# CTD_V02.net
KiCad netlist of a schematic drawn in EAGLE
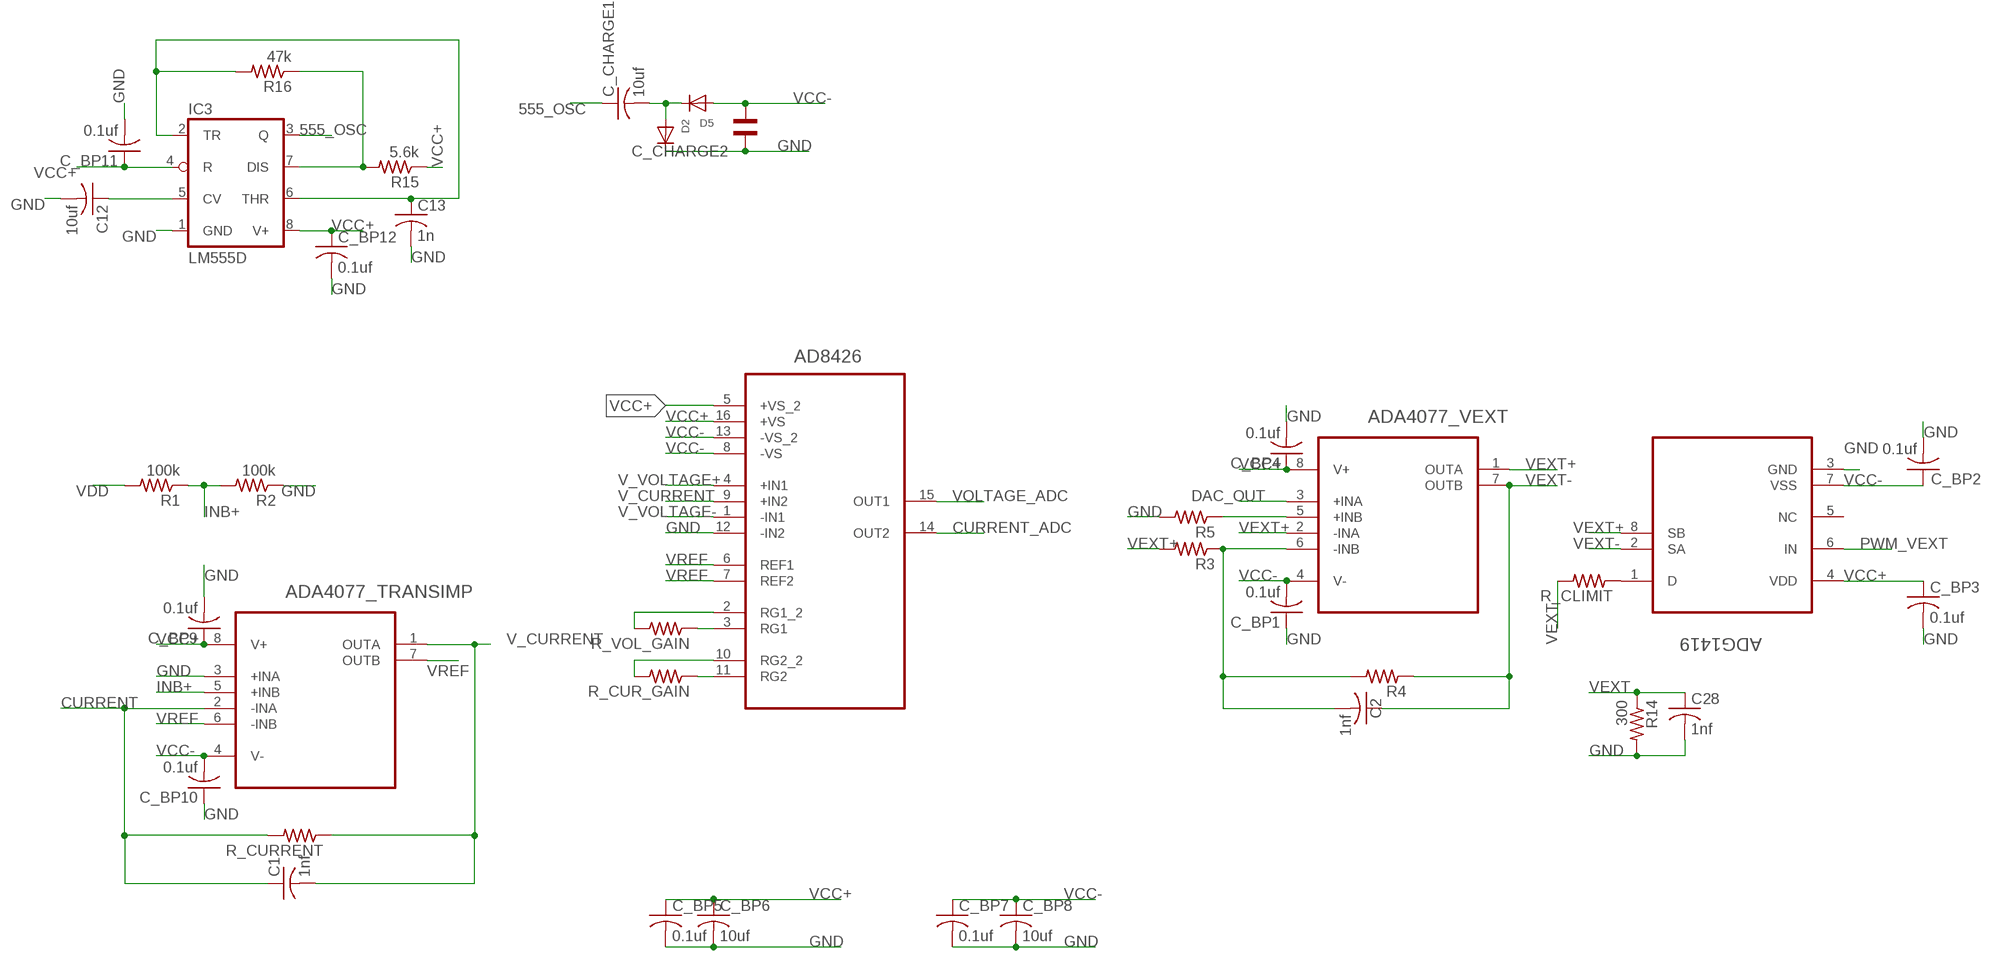
[diagram p0: schematic, sheet 1]
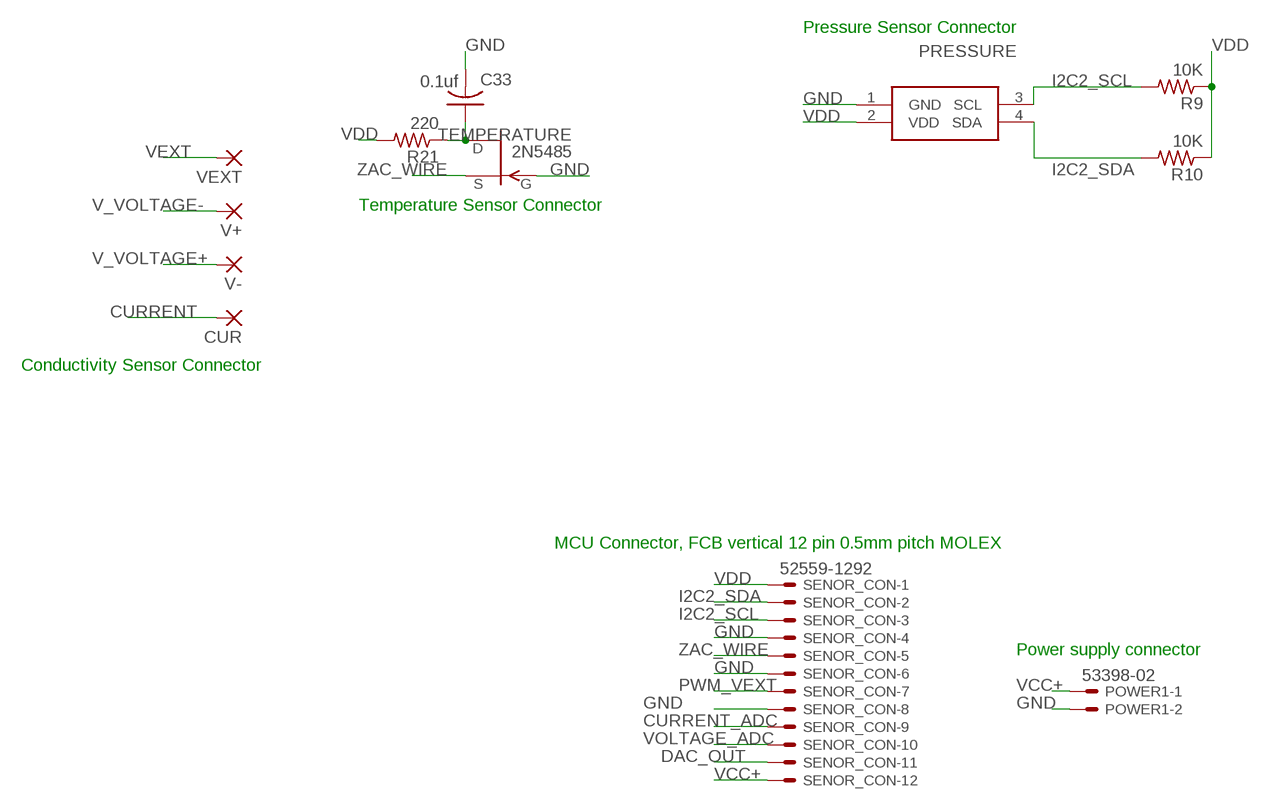
[diagram p1: schematic, sheet 2]
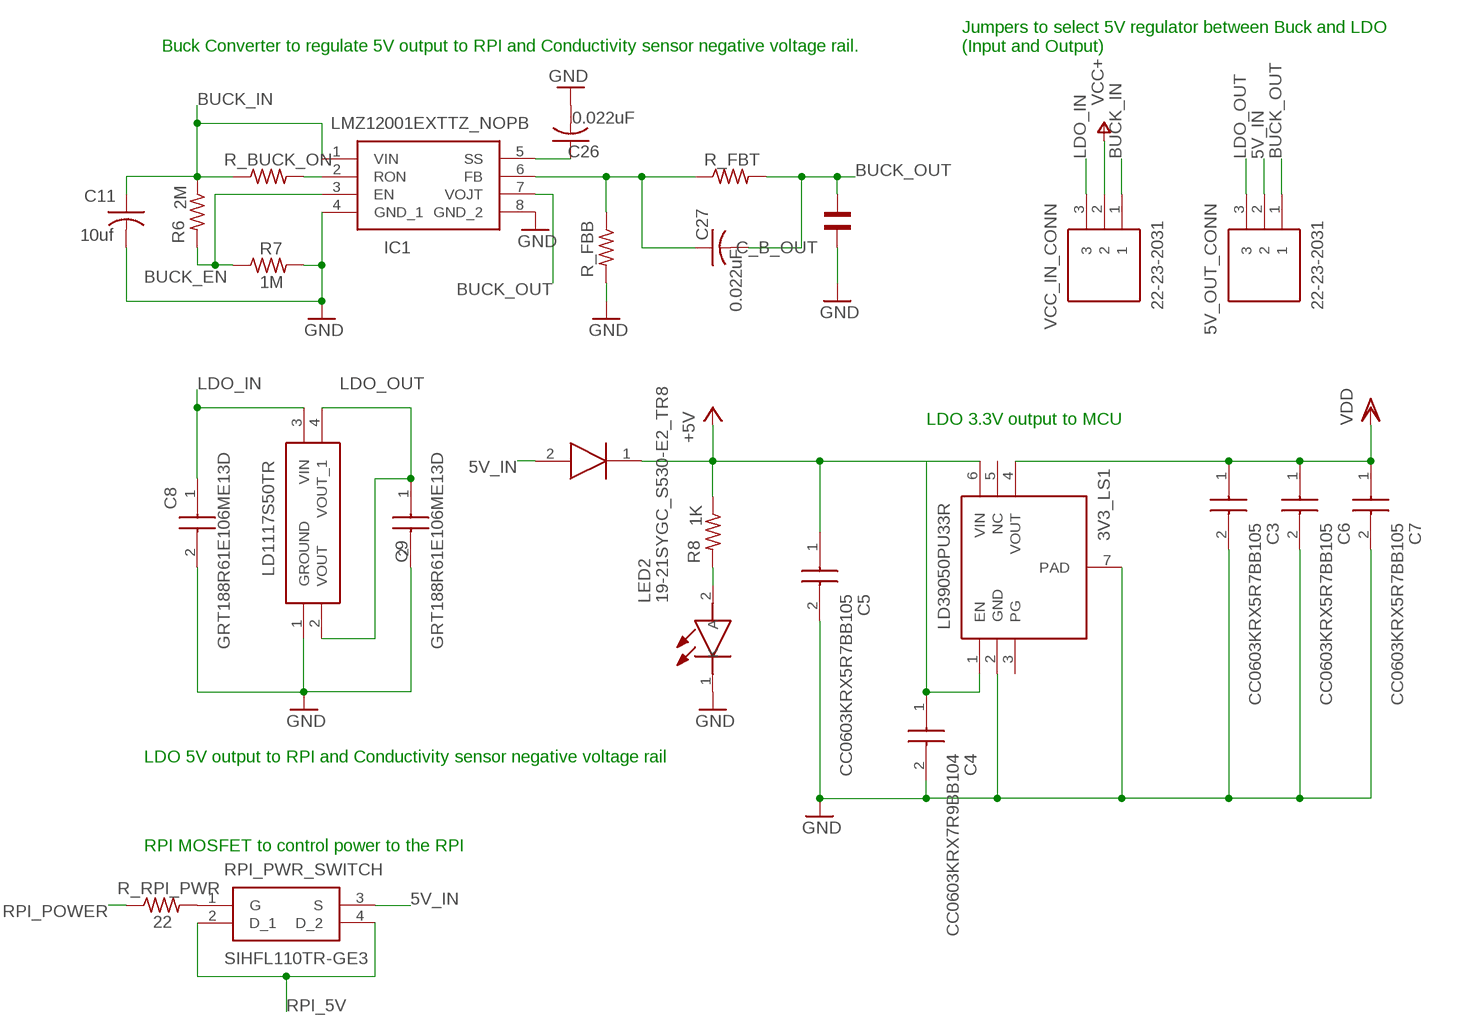
[diagram p2: schematic, sheet 3]
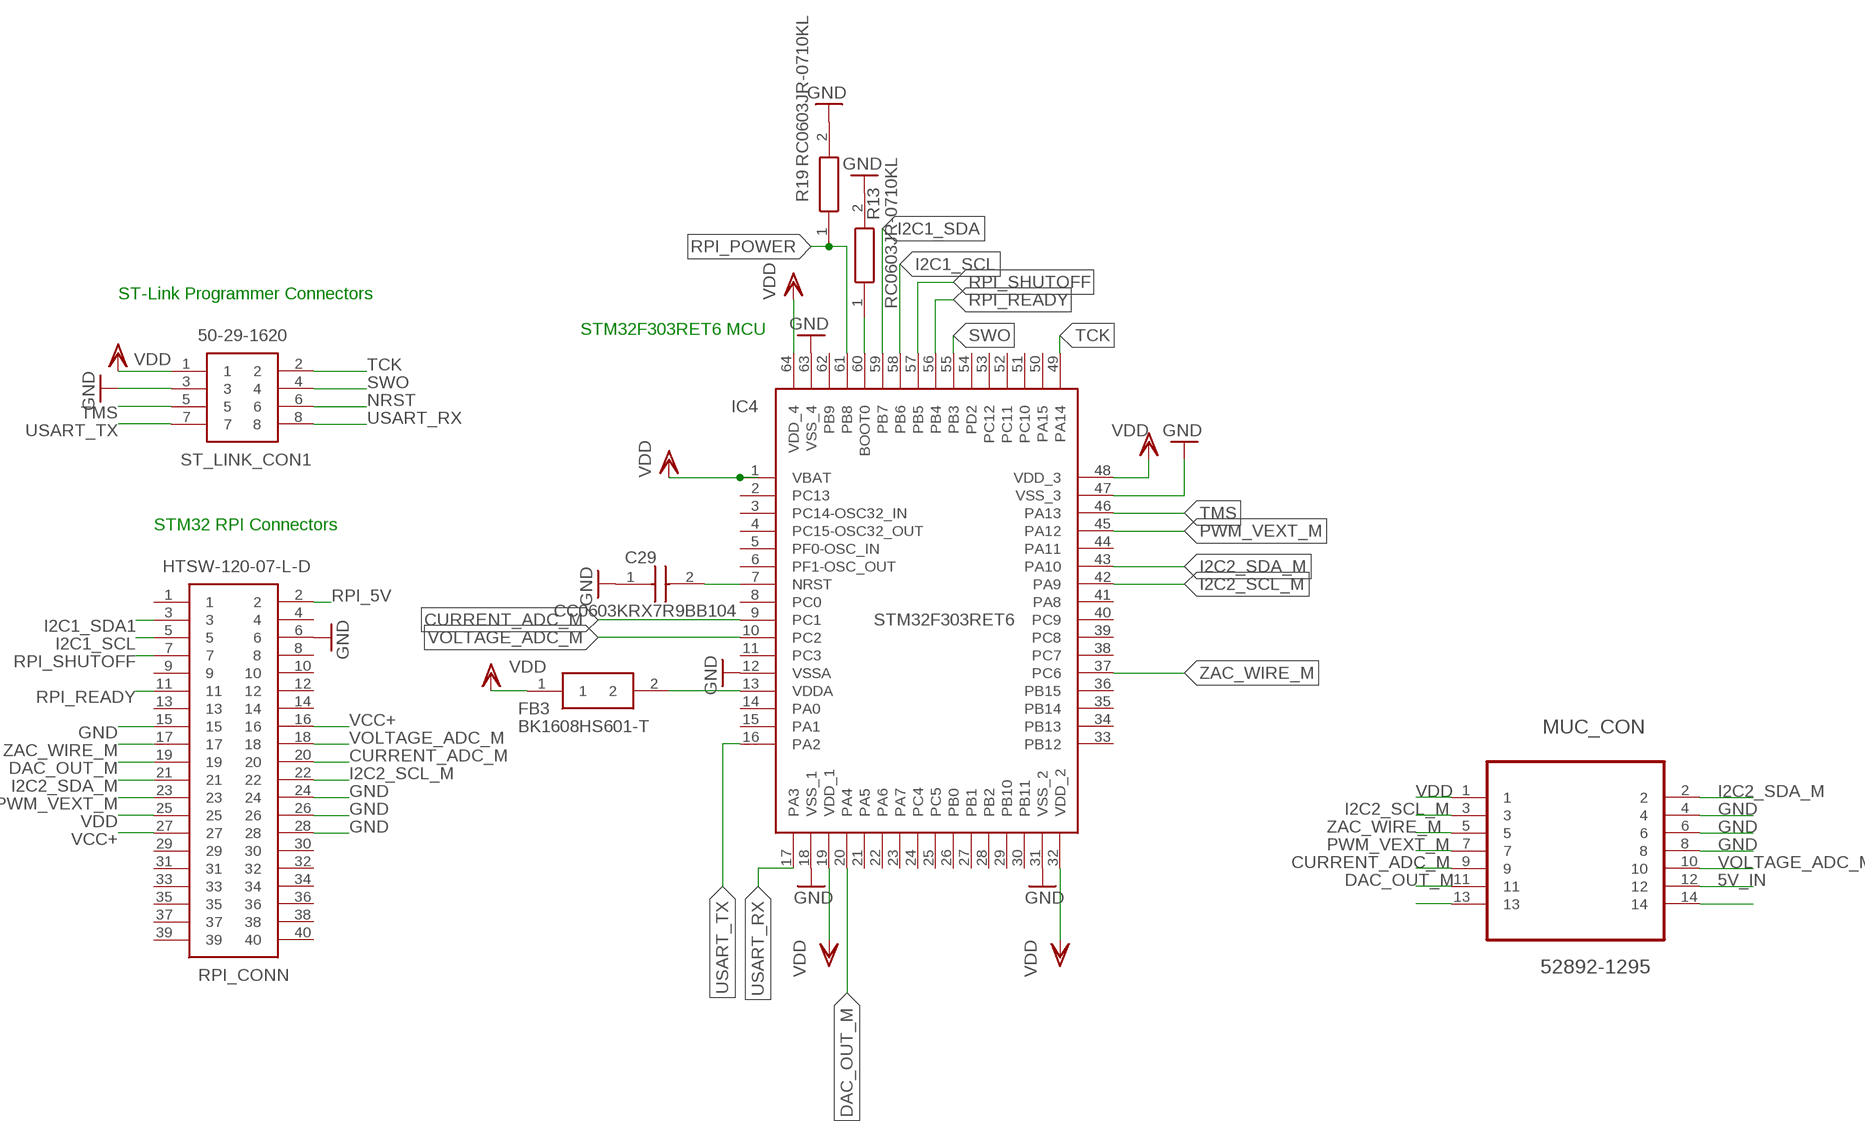
[diagram p3: schematic, sheet 4]

(export (version "E")
  (design (tool "Eeschema 10.0.6"))
  (components
    (comp (ref "C33")
      (value "0.1uf")
      (footprint "eagle-import:C0603")
      (libsource (lib "eagle-import") (part "C-USC0603"))
    )
    (comp (ref "CUR")
      (value "SMD2")
      (footprint "eagle-import:SMD1,27-2,54")
      (libsource (lib "eagle-import") (part "SMD2"))
    )
    (comp (ref "POWER1")
      (value "53398-02")
      (footprint "eagle-import:53398-02")
      (fields (field (name "MF") "MOLEX"))
      (libsource (lib "eagle-import") (part "53?-02398"))
    )
    (comp (ref "PRESSURE")
      (value "MS583702BA01-50")
      (footprint "eagle-import:MS583702BA0150")
      (fields (field (name "MOUSER_PART_NUMBER") "824-MS583702BA01-50"))
      (libsource (lib "eagle-import") (part "MS583702BA01-50"))
    )
    (comp (ref "R9")
      (value "10K")
      (footprint "eagle-import:R0603")
      (libsource (lib "eagle-import") (part "R-US_R0603"))
    )
    (comp (ref "R10")
      (value "10K")
      (footprint "eagle-import:R0603")
      (libsource (lib "eagle-import") (part "R-US_R0603"))
    )
    (comp (ref "R21")
      (value "220")
      (footprint "eagle-import:R0603")
      (libsource (lib "eagle-import") (part "R-US_R0603"))
    )
    (comp (ref "SENOR_CON")
      (value "52559-1292")
      (footprint "eagle-import:52559-1292")
      (fields (field (name "MF") "MOLEX"))
      (libsource (lib "eagle-import") (part "52559-1292"))
    )
    (comp (ref "TEMPERATURE")
      (value "2N5485")
      (footprint "eagle-import:TO92-")
      (libsource (lib "eagle-import") (part "?5482N5"))
    )
    (comp (ref "V+")
      (value "SMD2")
      (footprint "eagle-import:SMD1,27-2,54")
      (libsource (lib "eagle-import") (part "SMD2"))
    )
    (comp (ref "V-")
      (value "SMD2")
      (footprint "eagle-import:SMD1,27-2,54")
      (libsource (lib "eagle-import") (part "SMD2"))
    )
    (comp (ref "VEXT")
      (value "SMD2")
      (footprint "eagle-import:SMD1,27-2,54")
      (libsource (lib "eagle-import") (part "SMD2"))
    )
    (comp (ref "AD8426")
      (value "AD8426BCPZ-WP")
      (footprint "eagle-import:QFN65P400X400X100-16N")
      (fields (field (name "MF") "Analog Devices"))
      (libsource (lib "eagle-import") (part "AD8426BCPZ-WP"))
    )
    (comp (ref "ADA4077_TRANSIMP")
      (value "ADA4075-2ARZ")
      (footprint "eagle-import:SOIC127P600X175-8N")
      (fields (field (name "MPN") "ADA4077"))
      (libsource (lib "eagle-import") (part "ADA4075-2ARZ"))
    )
    (comp (ref "ADA4077_VEXT")
      (value "ADA4075-2ARZ")
      (footprint "eagle-import:SOIC127P600X175-8N")
      (fields (field (name "MPN") "ADA4077"))
      (libsource (lib "eagle-import") (part "ADA4075-2ARZ"))
    )
    (comp (ref "ADG1419")
      (value "ADG1419BRMZ")
      (footprint "eagle-import:SOP65P490X110-8N")
      (libsource (lib "eagle-import") (part "ADG1419BRMZ"))
    )
    (comp (ref "C1")
      (value "1nf")
      (footprint "eagle-import:C0603")
      (libsource (lib "eagle-import") (part "C-USC0603"))
    )
    (comp (ref "C2")
      (value "1nf")
      (footprint "eagle-import:C0603")
      (libsource (lib "eagle-import") (part "C-USC0603"))
    )
    (comp (ref "C12")
      (value "10uf")
      (footprint "eagle-import:C0603")
      (libsource (lib "eagle-import") (part "C-USC0603"))
    )
    (comp (ref "C13")
      (value "1n")
      (footprint "eagle-import:C0603")
      (libsource (lib "eagle-import") (part "C-USC0603"))
    )
    (comp (ref "C28")
      (value "1nf")
      (footprint "eagle-import:C0603")
      (libsource (lib "eagle-import") (part "C-USC0603"))
    )
    (comp (ref "C_BP1")
      (value "0.1uf")
      (footprint "eagle-import:C0603")
      (libsource (lib "eagle-import") (part "C-USC0603"))
    )
    (comp (ref "C_BP2")
      (value "0.1uf")
      (footprint "eagle-import:C0603")
      (libsource (lib "eagle-import") (part "C-USC0603"))
    )
    (comp (ref "C_BP3")
      (value "0.1uf")
      (footprint "eagle-import:C0603")
      (libsource (lib "eagle-import") (part "C-USC0603"))
    )
    (comp (ref "C_BP4")
      (value "0.1uf")
      (footprint "eagle-import:C0603")
      (libsource (lib "eagle-import") (part "C-USC0603"))
    )
    (comp (ref "C_BP5")
      (value "0.1uf")
      (footprint "eagle-import:C0603")
      (libsource (lib "eagle-import") (part "C-USC0603"))
    )
    (comp (ref "C_BP6")
      (value "10uf")
      (footprint "eagle-import:C0603")
      (libsource (lib "eagle-import") (part "C-USC0603"))
    )
    (comp (ref "C_BP7")
      (value "0.1uf")
      (footprint "eagle-import:C0603")
      (libsource (lib "eagle-import") (part "C-USC0603"))
    )
    (comp (ref "C_BP8")
      (value "10uf")
      (footprint "eagle-import:C0603")
      (libsource (lib "eagle-import") (part "C-USC0603"))
    )
    (comp (ref "C_BP9")
      (value "0.1uf")
      (footprint "eagle-import:C0603")
      (libsource (lib "eagle-import") (part "C-USC0603"))
    )
    (comp (ref "C_BP10")
      (value "0.1uf")
      (footprint "eagle-import:C0603")
      (libsource (lib "eagle-import") (part "C-USC0603"))
    )
    (comp (ref "C_BP11")
      (value "0.1uf")
      (footprint "eagle-import:C0603")
      (libsource (lib "eagle-import") (part "C-USC0603"))
    )
    (comp (ref "C_BP12")
      (value "0.1uf")
      (footprint "eagle-import:C0603")
      (libsource (lib "eagle-import") (part "C-USC0603"))
    )
    (comp (ref "C_CHARGE1")
      (value "10uf")
      (footprint "eagle-import:C0603")
      (libsource (lib "eagle-import") (part "C-USC0603"))
    )
    (comp (ref "C_CHARGE2")
      (value "WCAP-CSGP_1206_885012008001")
      (footprint "eagle-import:WCAP-CSGP_1206")
      (libsource (lib "eagle-import") (part "WCAP-CSGP_1206_885012008001"))
    )
    (comp (ref "D2")
      (value "DIODESOD-123")
      (footprint "eagle-import:SOD-123")
      (libsource (lib "eagle-import") (part "DIODESOD-123"))
    )
    (comp (ref "D5")
      (value "DIODESOD-123")
      (footprint "eagle-import:SOD-123")
      (libsource (lib "eagle-import") (part "DIODESOD-123"))
    )
    (comp (ref "IC3")
      (value "LM555D")
      (footprint "eagle-import:SO08")
      (libsource (lib "eagle-import") (part "555DLM"))
    )
    (comp (ref "R1")
      (value "100k")
      (footprint "eagle-import:R0603")
      (libsource (lib "eagle-import") (part "R-US_R0603"))
    )
    (comp (ref "R2")
      (value "100k")
      (footprint "eagle-import:R0603")
      (libsource (lib "eagle-import") (part "R-US_R0603"))
    )
    (comp (ref "R3")
      (value "R-US_R0603")
      (footprint "eagle-import:R0603")
      (libsource (lib "eagle-import") (part "R-US_R0603"))
    )
    (comp (ref "R4")
      (value "R-US_R0603")
      (footprint "eagle-import:R0603")
      (libsource (lib "eagle-import") (part "R-US_R0603"))
    )
    (comp (ref "R5")
      (value "R-US_R0603")
      (footprint "eagle-import:R0603")
      (libsource (lib "eagle-import") (part "R-US_R0603"))
    )
    (comp (ref "R14")
      (value "300")
      (footprint "eagle-import:R0603")
      (libsource (lib "eagle-import") (part "R-US_R0603"))
    )
    (comp (ref "R15")
      (value "5.6k")
      (footprint "eagle-import:R0603")
      (libsource (lib "eagle-import") (part "R-US_R0603"))
    )
    (comp (ref "R16")
      (value "47k")
      (footprint "eagle-import:R0603")
      (libsource (lib "eagle-import") (part "R-US_R0603"))
    )
    (comp (ref "R_CLIMIT")
      (value "R-US_R0603")
      (footprint "eagle-import:R0603")
      (libsource (lib "eagle-import") (part "R-US_R0603"))
    )
    (comp (ref "R_CURRENT")
      (value "R-US_R0603")
      (footprint "eagle-import:R0603")
      (libsource (lib "eagle-import") (part "R-US_R0603"))
    )
    (comp (ref "R_CUR_GAIN")
      (value "R-US_R0603")
      (footprint "eagle-import:R0603")
      (libsource (lib "eagle-import") (part "R-US_R0603"))
    )
    (comp (ref "R_VOL_GAIN")
      (value "R-US_R0603")
      (footprint "eagle-import:R0603")
      (libsource (lib "eagle-import") (part "R-US_R0603"))
    )
    (comp (ref "3V3_LS1")
      (value "LD39050PU33R")
      (footprint "eagle-import:SON95P300X300X100-7N")
      (fields (field (name "MOUSER_PART_NUMBER") "511-LD39050PU33R"))
      (libsource (lib "eagle-import") (part "LD39050PU33R"))
    )
    (comp (ref "5V_LS1")
      (value "LD1117S50TR")
      (footprint "eagle-import:SOT230P700X190-4N")
      (fields (field (name "MOUSER_PART_NUMBER") "511-LD1117S50"))
      (libsource (lib "eagle-import") (part "LD1117S50TR"))
    )
    (comp (ref "5V_OUT_CONN")
      (value "22-23-2031")
      (footprint "eagle-import:SHDR3W87P0X254_1X3_747X635X843")
      (fields (field (name "MOUSER_PART_NUMBER") "538-22-23-2031"))
      (libsource (lib "eagle-import") (part "22-23-2031"))
    )
    (comp (ref "C3")
      (value "CC0603KRX5R7BB105")
      (footprint "eagle-import:CAPC1608X90N")
      (fields (field (name "MOUSER_PART_NUMBER") "603-CC603KRX5R7BB105"))
      (libsource (lib "eagle-import") (part "CC0603KRX5R7BB105"))
    )
    (comp (ref "C4")
      (value "CC0603KRX7R9BB104")
      (footprint "eagle-import:CAPC1608X90N")
      (fields (field (name "MOUSER_PART_NUMBER") "603-CC603KRX7R9BB104"))
      (libsource (lib "eagle-import") (part "CC0603KRX7R9BB104"))
    )
    (comp (ref "C5")
      (value "CC0603KRX5R7BB105")
      (footprint "eagle-import:CAPC1608X90N")
      (fields (field (name "MOUSER_PART_NUMBER") "603-CC603KRX5R7BB105"))
      (libsource (lib "eagle-import") (part "CC0603KRX5R7BB105"))
    )
    (comp (ref "C6")
      (value "CC0603KRX5R7BB105")
      (footprint "eagle-import:CAPC1608X90N")
      (fields (field (name "MOUSER_PART_NUMBER") "603-CC603KRX5R7BB105"))
      (libsource (lib "eagle-import") (part "CC0603KRX5R7BB105"))
    )
    (comp (ref "C7")
      (value "CC0603KRX5R7BB105")
      (footprint "eagle-import:CAPC1608X90N")
      (fields (field (name "MOUSER_PART_NUMBER") "603-CC603KRX5R7BB105"))
      (libsource (lib "eagle-import") (part "CC0603KRX5R7BB105"))
    )
    (comp (ref "C8")
      (value "GRT188R61E106ME13D")
      (footprint "eagle-import:CAPC1608X100N")
      (fields (field (name "MOUSER_PART_NUMBER") "81-GRT188R61E106ME3D"))
      (libsource (lib "eagle-import") (part "GRT188R61E106ME13D"))
    )
    (comp (ref "C9")
      (value "GRT188R61E106ME13D")
      (footprint "eagle-import:CAPC1608X100N")
      (fields (field (name "MOUSER_PART_NUMBER") "81-GRT188R61E106ME3D"))
      (libsource (lib "eagle-import") (part "GRT188R61E106ME13D"))
    )
    (comp (ref "C11")
      (value "10uf")
      (footprint "eagle-import:C0603")
      (libsource (lib "eagle-import") (part "C-USC0603"))
    )
    (comp (ref "C26")
      (value "0.022uF")
      (footprint "eagle-import:C0603")
      (libsource (lib "eagle-import") (part "C-USC0603"))
    )
    (comp (ref "C27")
      (value "0.022uF")
      (footprint "eagle-import:C0603")
      (libsource (lib "eagle-import") (part "C-USC0603"))
    )
    (comp (ref "C_B_OUT")
      (value "WCAP-CSGP_1206_885012008001")
      (footprint "eagle-import:WCAP-CSGP_1206")
      (libsource (lib "eagle-import") (part "WCAP-CSGP_1206_885012008001"))
    )
    (comp (ref "D3")
      (value "STPS2L30A")
      (footprint "eagle-import:DIOM5126X265N")
      (fields (field (name "MOUSER_PART_NUMBER") "511-STPS2L30A"))
      (libsource (lib "eagle-import") (part "STPS2L30A"))
    )
    (comp (ref "IC1")
      (value "LMZ12001EXTTZ_NOPB")
      (footprint "eagle-import:NDW0007A")
      (fields
        (field (name "MANUFACTURER_PART_NUMBER") "LMZ12001EXTTZ/NOPB")
        (field (name "MOUSER_PART_NUMBER") "926-LMZ12001EXTTZNPB")
      )
      (libsource (lib "eagle-import") (part "LMZ12001EXTTZ_NOPB"))
    )
    (comp (ref "LED2")
      (value "19-21SYGC_S530-E2_TR8")
      (footprint "eagle-import:LEDC1608X90N")
      (fields
        (field (name "MANUFACTURER_PART_NUMBER") "19-21SYGC/S530-E2/TR8")
        (field (name "MOUSER_PART_NUMBER") "638-1921SYGCS530E2")
      )
      (libsource (lib "eagle-import") (part "19-21SYGC_S530-E2_TR8"))
    )
    (comp (ref "R6")
      (value "2M")
      (footprint "eagle-import:R0603")
      (libsource (lib "eagle-import") (part "R-US_R0603"))
    )
    (comp (ref "R7")
      (value "1M")
      (footprint "eagle-import:R0603")
      (libsource (lib "eagle-import") (part "R-US_R0603"))
    )
    (comp (ref "R8")
      (value "1K")
      (footprint "eagle-import:R0603")
      (libsource (lib "eagle-import") (part "R-US_R0603"))
    )
    (comp (ref "RPI_PWR_SWITCH")
      (value "SIHFL110TR-GE3")
      (footprint "eagle-import:SOT230P700X180-4N")
      (fields (field (name "MOUSER_PART_NUMBER") "78-SIHFL110TR-GE3"))
      (libsource (lib "eagle-import") (part "SIHFL110TR-GE3"))
    )
    (comp (ref "R_BUCK_ON")
      (value "R-US_R0603")
      (footprint "eagle-import:R0603")
      (libsource (lib "eagle-import") (part "R-US_R0603"))
    )
    (comp (ref "R_FBB")
      (value "R-US_R0603")
      (footprint "eagle-import:R0603")
      (libsource (lib "eagle-import") (part "R-US_R0603"))
    )
    (comp (ref "R_FBT")
      (value "R-US_R0603")
      (footprint "eagle-import:R0603")
      (libsource (lib "eagle-import") (part "R-US_R0603"))
    )
    (comp (ref "R_RPI_PWR")
      (value "22")
      (footprint "eagle-import:R0603")
      (libsource (lib "eagle-import") (part "R-US_R0603"))
    )
    (comp (ref "VCC_IN_CONN")
      (value "22-23-2031")
      (footprint "eagle-import:SHDR3W87P0X254_1X3_747X635X843")
      (fields (field (name "MOUSER_PART_NUMBER") "538-22-23-2031"))
      (libsource (lib "eagle-import") (part "22-23-2031"))
    )
    (comp (ref "C29")
      (value "CC0603KRX7R9BB104")
      (footprint "eagle-import:CAPC1608X90N")
      (fields (field (name "MOUSER_PART_NUMBER") "603-CC603KRX7R9BB104"))
      (libsource (lib "eagle-import") (part "CC0603KRX7R9BB104"))
    )
    (comp (ref "FB3")
      (value "BK1608HS601-T")
      (footprint "eagle-import:BEADC1608X95N")
      (fields (field (name "MOUSER_PART_NUMBER") "963-BK1608HS601-T"))
      (libsource (lib "eagle-import") (part "BK1608HS601-T"))
    )
    (comp (ref "IC4")
      (value "STM32F303RET6")
      (footprint "eagle-import:QFP50P1200X1200X160-64N")
      (fields (field (name "MOUSER_PART_NUMBER") "511-STM32F303RET6"))
      (libsource (lib "eagle-import") (part "STM32F303RET6"))
    )
    (comp (ref "MUC_CON")
      (value "52892-1295")
      (footprint "eagle-import:MOLEX_52892-1295")
      (libsource (lib "eagle-import") (part "52892-1295"))
    )
    (comp (ref "R13")
      (value "RC0603JR-0710KL")
      (footprint "eagle-import:RESC1608X55N")
      (fields (field (name "MOUSER_PART_NUMBER") "603-RC0603JR-0710KL"))
      (libsource (lib "eagle-import") (part "RC0603JR-0710KL"))
    )
    (comp (ref "R19")
      (value "RC0603JR-0710KL")
      (footprint "eagle-import:RESC1608X55N")
      (fields (field (name "MOUSER_PART_NUMBER") "603-RC0603JR-0710KL"))
      (libsource (lib "eagle-import") (part "RC0603JR-0710KL"))
    )
    (comp (ref "RPI_CONN")
      (value "HTSW-120-07-L-D")
      (footprint "eagle-import:SAMTEC_HTSW-120-07-L")
      (fields (field (name "MOUSER_PART_NUMBER") "200-HTSW12007LD"))
      (libsource (lib "eagle-import") (part "HTSW-120-07-L-D"))
    )
    (comp (ref "ST_LINK_CON1")
      (value "50-29-1620")
      (footprint "eagle-import:50291620")
      (fields (field (name "MOUSER_PART_NUMBER") "538-50-29-1620"))
      (libsource (lib "eagle-import") (part "50-29-1620"))
    )
  )
  (nets
    (net (code "1") (name "+5V") (class "Default")
      (node (ref "3V3_LS1") (pin "1") (pinfunction "EN_1") (pintype "input"))
      (node (ref "3V3_LS1") (pin "6") (pinfunction "VIN_6") (pintype "power_in"))
      (node (ref "C4") (pin "1") (pinfunction "1_1") (pintype "bidirectional"))
      (node (ref "C5") (pin "1") (pinfunction "1_1") (pintype "bidirectional"))
      (node (ref "D3") (pin "1") (pinfunction "K_1") (pintype "bidirectional"))
      (node (ref "R8") (pin "1") (pinfunction "1_1") (pintype "passive"))
    )
    (net (code "2") (name "5V_IN") (class "Default")
      (node (ref "5V_OUT_CONN") (pin "2") (pinfunction "2_2") (pintype "bidirectional"))
      (node (ref "D3") (pin "2") (pinfunction "A_2") (pintype "bidirectional"))
      (node (ref "MUC_CON") (pin "12") (pinfunction "12_12") (pintype "passive"))
      (node (ref "RPI_PWR_SWITCH") (pin "3") (pinfunction "S_3") (pintype "bidirectional"))
    )
    (net (code "3") (name "555_OSC") (class "Default")
      (node (ref "C_CHARGE1") (pin "1") (pinfunction "1_1") (pintype "passive"))
      (node (ref "IC3") (pin "3") (pinfunction "Q_3") (pintype "output"))
    )
    (net (code "4") (name "BUCK_EN") (class "Default")
      (node (ref "IC1") (pin "3") (pinfunction "EN_3") (pintype "bidirectional"))
      (node (ref "R6") (pin "2") (pinfunction "2_2") (pintype "passive"))
      (node (ref "R7") (pin "1") (pinfunction "1_1") (pintype "passive"))
    )
    (net (code "5") (name "BUCK_IN") (class "Default")
      (node (ref "C11") (pin "1") (pinfunction "1_1") (pintype "passive"))
      (node (ref "IC1") (pin "1") (pinfunction "VIN_1") (pintype "bidirectional"))
      (node (ref "R6") (pin "1") (pinfunction "1_1") (pintype "passive"))
      (node (ref "R_BUCK_ON") (pin "1") (pinfunction "1_1") (pintype "passive"))
      (node (ref "VCC_IN_CONN") (pin "1") (pinfunction "1_1") (pintype "bidirectional"))
    )
    (net (code "6") (name "BUCK_OUT") (class "Default")
      (node (ref "5V_OUT_CONN") (pin "1") (pinfunction "1_1") (pintype "bidirectional"))
      (node (ref "C27") (pin "2") (pinfunction "2_2") (pintype "passive"))
      (node (ref "C_B_OUT") (pin "1") (pinfunction "1_1") (pintype "passive"))
      (node (ref "IC1") (pin "7") (pinfunction "VOJT_7") (pintype "bidirectional"))
      (node (ref "R_FBT") (pin "2") (pinfunction "2_2") (pintype "passive"))
    )
    (net (code "7") (name "CURRENT") (class "Default")
      (node (ref "ADA4077_TRANSIMP") (pin "2") (pinfunction "-INA_2") (pintype "input"))
      (node (ref "C1") (pin "1") (pinfunction "1_1") (pintype "passive"))
      (node (ref "CUR") (pin "1") (pinfunction "P_1") (pintype "passive"))
      (node (ref "R_CURRENT") (pin "2") (pinfunction "2_2") (pintype "passive"))
    )
    (net (code "8") (name "CURRENT_ADC") (class "Default")
      (node (ref "AD8426") (pin "14") (pinfunction "OUT2_14") (pintype "passive"))
      (node (ref "SENOR_CON") (pin "9") (pinfunction "S_9") (pintype "passive"))
    )
    (net (code "9") (name "CURRENT_ADC_M") (class "Default")
      (node (ref "IC4") (pin "9") (pinfunction "PC1_9") (pintype "bidirectional"))
      (node (ref "MUC_CON") (pin "9") (pinfunction "9_9") (pintype "passive"))
      (node (ref "RPI_CONN") (pin "20") (pinfunction "20_20") (pintype "bidirectional"))
    )
    (net (code "10") (name "DAC_OUT") (class "Default")
      (node (ref "ADA4077_VEXT") (pin "3") (pinfunction "+INA_3") (pintype "input"))
      (node (ref "SENOR_CON") (pin "11") (pinfunction "S_11") (pintype "passive"))
    )
    (net (code "11") (name "DAC_OUT_M") (class "Default")
      (node (ref "IC4") (pin "20") (pinfunction "PA4_20") (pintype "bidirectional"))
      (node (ref "MUC_CON") (pin "11") (pinfunction "11_11") (pintype "passive"))
      (node (ref "RPI_CONN") (pin "19") (pinfunction "19_19") (pintype "bidirectional"))
    )
    (net (code "12") (name "GND") (class "Default")
      (node (ref "3V3_LS1") (pin "2") (pinfunction "GND_2") (pintype "power_in"))
      (node (ref "3V3_LS1") (pin "7") (pinfunction "PAD_7") (pintype "power_in"))
      (node (ref "5V_LS1") (pin "1") (pinfunction "GROUND_1") (pintype "bidirectional"))
      (node (ref "AD8426") (pin "12") (pinfunction "-IN2_12") (pintype "passive"))
      (node (ref "ADA4077_TRANSIMP") (pin "3") (pinfunction "+INA_3") (pintype "input"))
      (node (ref "ADG1419") (pin "3") (pinfunction "GND_3") (pintype "passive"))
      (node (ref "C11") (pin "2") (pinfunction "2_2") (pintype "passive"))
      (node (ref "C12") (pin "2") (pinfunction "2_2") (pintype "passive"))
      (node (ref "C13") (pin "2") (pinfunction "2_2") (pintype "passive"))
      (node (ref "C26") (pin "2") (pinfunction "2_2") (pintype "passive"))
      (node (ref "C28") (pin "2") (pinfunction "2_2") (pintype "passive"))
      (node (ref "C29") (pin "1") (pinfunction "1_1") (pintype "bidirectional"))
      (node (ref "C3") (pin "2") (pinfunction "2_2") (pintype "bidirectional"))
      (node (ref "C33") (pin "2") (pinfunction "2_2") (pintype "passive"))
      (node (ref "C4") (pin "2") (pinfunction "2_2") (pintype "bidirectional"))
      (node (ref "C5") (pin "2") (pinfunction "2_2") (pintype "bidirectional"))
      (node (ref "C6") (pin "2") (pinfunction "2_2") (pintype "bidirectional"))
      (node (ref "C7") (pin "2") (pinfunction "2_2") (pintype "bidirectional"))
      (node (ref "C8") (pin "2") (pinfunction "2_2") (pintype "bidirectional"))
      (node (ref "C9") (pin "2") (pinfunction "2_2") (pintype "bidirectional"))
      (node (ref "C_BP1") (pin "1") (pinfunction "1_1") (pintype "passive"))
      (node (ref "C_BP10") (pin "1") (pinfunction "1_1") (pintype "passive"))
      (node (ref "C_BP11") (pin "2") (pinfunction "2_2") (pintype "passive"))
      (node (ref "C_BP12") (pin "2") (pinfunction "2_2") (pintype "passive"))
      (node (ref "C_BP2") (pin "2") (pinfunction "2_2") (pintype "passive"))
      (node (ref "C_BP3") (pin "2") (pinfunction "2_2") (pintype "passive"))
      (node (ref "C_BP4") (pin "2") (pinfunction "2_2") (pintype "passive"))
      (node (ref "C_BP5") (pin "2") (pinfunction "2_2") (pintype "passive"))
      (node (ref "C_BP6") (pin "2") (pinfunction "2_2") (pintype "passive"))
      (node (ref "C_BP7") (pin "2") (pinfunction "2_2") (pintype "passive"))
      (node (ref "C_BP8") (pin "2") (pinfunction "2_2") (pintype "passive"))
      (node (ref "C_BP9") (pin "2") (pinfunction "2_2") (pintype "passive"))
      (node (ref "C_B_OUT") (pin "2") (pinfunction "2_2") (pintype "passive"))
      (node (ref "C_CHARGE2") (pin "2") (pinfunction "2_2") (pintype "passive"))
      (node (ref "D2") (pin "C") (pinfunction "C_C") (pintype "passive"))
      (node (ref "IC1") (pin "4") (pinfunction "GND_1_4") (pintype "bidirectional"))
      (node (ref "IC1") (pin "8") (pinfunction "GND_2_8") (pintype "bidirectional"))
      (node (ref "IC3") (pin "1") (pinfunction "GND_1") (pintype "power_in"))
      (node (ref "IC4") (pin "12") (pinfunction "VSSA_12") (pintype "power_in"))
      (node (ref "IC4") (pin "18") (pinfunction "VSS_1_18") (pintype "power_in"))
      (node (ref "IC4") (pin "31") (pinfunction "VSS_2_31") (pintype "power_in"))
      (node (ref "IC4") (pin "47") (pinfunction "VSS_3_47") (pintype "power_in"))
      (node (ref "IC4") (pin "63") (pinfunction "VSS_4_63") (pintype "power_in"))
      (node (ref "LED2") (pin "1") (pinfunction "K_1") (pintype "bidirectional"))
      (node (ref "MUC_CON") (pin "4") (pinfunction "4_4") (pintype "passive"))
      (node (ref "MUC_CON") (pin "6") (pinfunction "6_6") (pintype "passive"))
      (node (ref "MUC_CON") (pin "8") (pinfunction "8_8") (pintype "passive"))
      (node (ref "POWER1") (pin "2") (pinfunction "S_2") (pintype "passive"))
      (node (ref "PRESSURE") (pin "1") (pinfunction "GND_1") (pintype "bidirectional"))
      (node (ref "R13") (pin "2") (pinfunction "2_2") (pintype "bidirectional"))
      (node (ref "R14") (pin "2") (pinfunction "2_2") (pintype "passive"))
      (node (ref "R19") (pin "2") (pinfunction "2_2") (pintype "bidirectional"))
      (node (ref "R2") (pin "1") (pinfunction "1_1") (pintype "passive"))
      (node (ref "R5") (pin "2") (pinfunction "2_2") (pintype "passive"))
      (node (ref "R7") (pin "2") (pinfunction "2_2") (pintype "passive"))
      (node (ref "RPI_CONN") (pin "15") (pinfunction "15_15") (pintype "bidirectional"))
      (node (ref "RPI_CONN") (pin "24") (pinfunction "24_24") (pintype "bidirectional"))
      (node (ref "RPI_CONN") (pin "26") (pinfunction "26_26") (pintype "bidirectional"))
      (node (ref "RPI_CONN") (pin "28") (pinfunction "28_28") (pintype "bidirectional"))
      (node (ref "RPI_CONN") (pin "6") (pinfunction "6_6") (pintype "bidirectional"))
      (node (ref "R_FBB") (pin "2") (pinfunction "2_2") (pintype "passive"))
      (node (ref "SENOR_CON") (pin "4") (pinfunction "S_4") (pintype "passive"))
      (node (ref "SENOR_CON") (pin "6") (pinfunction "S_6") (pintype "passive"))
      (node (ref "SENOR_CON") (pin "8") (pinfunction "S_8") (pintype "passive"))
      (node (ref "ST_LINK_CON1") (pin "3") (pinfunction "3_3") (pintype "bidirectional"))
      (node (ref "TEMPERATURE") (pin "1") (pinfunction "G_1") (pintype "passive"))
    )
    (net (code "13") (name "I2C1_SCL") (class "Default")
      (node (ref "IC4") (pin "58") (pinfunction "PB6_58") (pintype "bidirectional"))
      (node (ref "RPI_CONN") (pin "5") (pinfunction "5_5") (pintype "bidirectional"))
    )
    (net (code "14") (name "I2C1_SDA") (class "Default")
      (node (ref "IC4") (pin "59") (pinfunction "PB7_59") (pintype "bidirectional"))
    )
    (net (code "15") (name "I2C1_SDA1") (class "Default")
      (node (ref "RPI_CONN") (pin "3") (pinfunction "3_3") (pintype "bidirectional"))
    )
    (net (code "16") (name "I2C2_SCL") (class "Default")
      (node (ref "PRESSURE") (pin "3") (pinfunction "SCL_3") (pintype "bidirectional"))
      (node (ref "R9") (pin "2") (pinfunction "2_2") (pintype "passive"))
      (node (ref "SENOR_CON") (pin "3") (pinfunction "S_3") (pintype "passive"))
    )
    (net (code "17") (name "I2C2_SCL_M") (class "Default")
      (node (ref "IC4") (pin "42") (pinfunction "PA9_42") (pintype "bidirectional"))
      (node (ref "MUC_CON") (pin "3") (pinfunction "3_3") (pintype "passive"))
      (node (ref "RPI_CONN") (pin "22") (pinfunction "22_22") (pintype "bidirectional"))
    )
    (net (code "18") (name "I2C2_SDA") (class "Default")
      (node (ref "PRESSURE") (pin "4") (pinfunction "SDA_4") (pintype "bidirectional"))
      (node (ref "R10") (pin "2") (pinfunction "2_2") (pintype "passive"))
      (node (ref "SENOR_CON") (pin "2") (pinfunction "S_2") (pintype "passive"))
    )
    (net (code "19") (name "I2C2_SDA_M") (class "Default")
      (node (ref "IC4") (pin "43") (pinfunction "PA10_43") (pintype "bidirectional"))
      (node (ref "MUC_CON") (pin "2") (pinfunction "2_2") (pintype "passive"))
      (node (ref "RPI_CONN") (pin "21") (pinfunction "21_21") (pintype "bidirectional"))
    )
    (net (code "20") (name "INB+") (class "Default")
      (node (ref "ADA4077_TRANSIMP") (pin "5") (pinfunction "+INB_5") (pintype "input"))
      (node (ref "R1") (pin "1") (pinfunction "1_1") (pintype "passive"))
      (node (ref "R2") (pin "2") (pinfunction "2_2") (pintype "passive"))
    )
    (net (code "21") (name "LDO_IN") (class "Default")
      (node (ref "5V_LS1") (pin "3") (pinfunction "VIN_3") (pintype "input"))
      (node (ref "C8") (pin "1") (pinfunction "1_1") (pintype "bidirectional"))
      (node (ref "VCC_IN_CONN") (pin "3") (pinfunction "3_3") (pintype "bidirectional"))
    )
    (net (code "22") (name "LDO_OUT") (class "Default")
      (node (ref "5V_LS1") (pin "2") (pinfunction "VOUT_2") (pintype "output"))
      (node (ref "5V_LS1") (pin "4") (pinfunction "VOUT_1_4") (pintype "output"))
      (node (ref "5V_OUT_CONN") (pin "3") (pinfunction "3_3") (pintype "bidirectional"))
      (node (ref "C9") (pin "1") (pinfunction "1_1") (pintype "bidirectional"))
    )
    (net (code "23") (name "NRST") (class "Default")
      (node (ref "C29") (pin "2") (pinfunction "2_2") (pintype "bidirectional"))
      (node (ref "IC4") (pin "7") (pinfunction "NRST_7") (pintype "bidirectional"))
      (node (ref "ST_LINK_CON1") (pin "6") (pinfunction "6_6") (pintype "bidirectional"))
    )
    (net (code "24") (name "Net-(AD8426-RG1)") (class "Default")
      (node (ref "AD8426") (pin "3") (pinfunction "RG1_3") (pintype "passive"))
      (node (ref "R_VOL_GAIN") (pin "1") (pinfunction "1_1") (pintype "passive"))
    )
    (net (code "25") (name "Net-(AD8426-RG1_2)") (class "Default")
      (node (ref "AD8426") (pin "2") (pinfunction "RG1_2_2") (pintype "passive"))
      (node (ref "R_VOL_GAIN") (pin "2") (pinfunction "2_2") (pintype "passive"))
    )
    (net (code "26") (name "Net-(AD8426-RG2)") (class "Default")
      (node (ref "AD8426") (pin "11") (pinfunction "RG2_11") (pintype "passive"))
      (node (ref "R_CUR_GAIN") (pin "1") (pinfunction "1_1") (pintype "passive"))
    )
    (net (code "27") (name "Net-(AD8426-RG2_2)") (class "Default")
      (node (ref "AD8426") (pin "10") (pinfunction "RG2_2_10") (pintype "passive"))
      (node (ref "R_CUR_GAIN") (pin "2") (pinfunction "2_2") (pintype "passive"))
    )
    (net (code "28") (name "Net-(ADA4077_VEXT-+INB)") (class "Default")
      (node (ref "ADA4077_VEXT") (pin "5") (pinfunction "+INB_5") (pintype "input"))
      (node (ref "R5") (pin "1") (pinfunction "1_1") (pintype "passive"))
    )
    (net (code "29") (name "Net-(ADA4077_VEXT--INB)") (class "Default")
      (node (ref "ADA4077_VEXT") (pin "6") (pinfunction "-INB_6") (pintype "input"))
      (node (ref "C2") (pin "2") (pinfunction "2_2") (pintype "passive"))
      (node (ref "R3") (pin "1") (pinfunction "1_1") (pintype "passive"))
      (node (ref "R4") (pin "2") (pinfunction "2_2") (pintype "passive"))
    )
    (net (code "30") (name "Net-(ADG1419-D)") (class "Default")
      (node (ref "ADG1419") (pin "1") (pinfunction "D_1") (pintype "bidirectional"))
      (node (ref "R_CLIMIT") (pin "1") (pinfunction "1_1") (pintype "passive"))
    )
    (net (code "31") (name "Net-(C_CHARGE1-Pad2)") (class "Default")
      (node (ref "C_CHARGE1") (pin "2") (pinfunction "2_2") (pintype "passive"))
      (node (ref "D2") (pin "A") (pinfunction "A_A") (pintype "passive"))
      (node (ref "D5") (pin "C") (pinfunction "C_C") (pintype "passive"))
    )
    (net (code "32") (name "Net-(IC1-FB)") (class "Default")
      (node (ref "C27") (pin "1") (pinfunction "1_1") (pintype "passive"))
      (node (ref "IC1") (pin "6") (pinfunction "FB_6") (pintype "bidirectional"))
      (node (ref "R_FBB") (pin "1") (pinfunction "1_1") (pintype "passive"))
      (node (ref "R_FBT") (pin "1") (pinfunction "1_1") (pintype "passive"))
    )
    (net (code "33") (name "Net-(IC1-RON)") (class "Default")
      (node (ref "IC1") (pin "2") (pinfunction "RON_2") (pintype "bidirectional"))
      (node (ref "R_BUCK_ON") (pin "2") (pinfunction "2_2") (pintype "passive"))
    )
    (net (code "34") (name "Net-(IC1-SS)") (class "Default")
      (node (ref "C26") (pin "1") (pinfunction "1_1") (pintype "passive"))
      (node (ref "IC1") (pin "5") (pinfunction "SS_5") (pintype "bidirectional"))
    )
    (net (code "35") (name "Net-(IC3-CV)") (class "Default")
      (node (ref "C12") (pin "1") (pinfunction "1_1") (pintype "passive"))
      (node (ref "IC3") (pin "5") (pinfunction "CV_5") (pintype "input"))
    )
    (net (code "36") (name "Net-(IC3-DIS)") (class "Default")
      (node (ref "IC3") (pin "7") (pinfunction "DIS_7") (pintype "input"))
      (node (ref "R15") (pin "2") (pinfunction "2_2") (pintype "passive"))
      (node (ref "R16") (pin "1") (pinfunction "1_1") (pintype "passive"))
    )
    (net (code "37") (name "Net-(IC3-THR)") (class "Default")
      (node (ref "C13") (pin "1") (pinfunction "1_1") (pintype "passive"))
      (node (ref "IC3") (pin "2") (pinfunction "TR_2") (pintype "input"))
      (node (ref "IC3") (pin "6") (pinfunction "THR_6") (pintype "input"))
      (node (ref "R16") (pin "2") (pinfunction "2_2") (pintype "passive"))
    )
    (net (code "38") (name "Net-(IC4-BOOT0)") (class "Default")
      (node (ref "IC4") (pin "60") (pinfunction "BOOT0_60") (pintype "bidirectional"))
      (node (ref "R13") (pin "1") (pinfunction "1_1") (pintype "bidirectional"))
    )
    (net (code "39") (name "Net-(IC4-VDDA)") (class "Default")
      (node (ref "FB3") (pin "2") (pinfunction "2_2") (pintype "bidirectional"))
      (node (ref "IC4") (pin "13") (pinfunction "VDDA_13") (pintype "power_in"))
    )
    (net (code "40") (name "Net-(LED2-A)") (class "Default")
      (node (ref "LED2") (pin "2") (pinfunction "A_2") (pintype "bidirectional"))
      (node (ref "R8") (pin "2") (pinfunction "2_2") (pintype "passive"))
    )
    (net (code "41") (name "Net-(RPI_PWR_SWITCH-G)") (class "Default")
      (node (ref "RPI_PWR_SWITCH") (pin "1") (pinfunction "G_1") (pintype "bidirectional"))
      (node (ref "R_RPI_PWR") (pin "2") (pinfunction "2_2") (pintype "passive"))
    )
    (net (code "42") (name "Net-(TEMPERATURE-D)") (class "Default")
      (node (ref "C33") (pin "1") (pinfunction "1_1") (pintype "passive"))
      (node (ref "R21") (pin "1") (pinfunction "1_1") (pintype "passive"))
      (node (ref "TEMPERATURE") (pin "3") (pinfunction "D_3") (pintype "passive"))
    )
    (net (code "43") (name "PWM_VEXT") (class "Default")
      (node (ref "ADG1419") (pin "6") (pinfunction "IN_6") (pintype "input"))
      (node (ref "SENOR_CON") (pin "7") (pinfunction "S_7") (pintype "passive"))
    )
    (net (code "44") (name "PWM_VEXT_M") (class "Default")
      (node (ref "IC4") (pin "45") (pinfunction "PA12_45") (pintype "bidirectional"))
      (node (ref "MUC_CON") (pin "7") (pinfunction "7_7") (pintype "passive"))
      (node (ref "RPI_CONN") (pin "23") (pinfunction "23_23") (pintype "bidirectional"))
    )
    (net (code "45") (name "RPI_5V") (class "Default")
      (node (ref "RPI_CONN") (pin "2") (pinfunction "2_2") (pintype "bidirectional"))
      (node (ref "RPI_PWR_SWITCH") (pin "2") (pinfunction "D_1_2") (pintype "bidirectional"))
      (node (ref "RPI_PWR_SWITCH") (pin "4") (pinfunction "D_2_4") (pintype "bidirectional"))
    )
    (net (code "46") (name "RPI_POWER") (class "Default")
      (node (ref "IC4") (pin "61") (pinfunction "PB8_61") (pintype "bidirectional"))
      (node (ref "R19") (pin "1") (pinfunction "1_1") (pintype "bidirectional"))
      (node (ref "R_RPI_PWR") (pin "1") (pinfunction "1_1") (pintype "passive"))
    )
    (net (code "47") (name "RPI_READY") (class "Default")
      (node (ref "IC4") (pin "56") (pinfunction "PB4_56") (pintype "bidirectional"))
      (node (ref "RPI_CONN") (pin "11") (pinfunction "11_11") (pintype "bidirectional"))
    )
    (net (code "48") (name "RPI_SHUTOFF") (class "Default")
      (node (ref "IC4") (pin "57") (pinfunction "PB5_57") (pintype "bidirectional"))
      (node (ref "RPI_CONN") (pin "7") (pinfunction "7_7") (pintype "bidirectional"))
    )
    (net (code "49") (name "SWO") (class "Default")
      (node (ref "IC4") (pin "55") (pinfunction "PB3_55") (pintype "bidirectional"))
      (node (ref "ST_LINK_CON1") (pin "4") (pinfunction "4_4") (pintype "bidirectional"))
    )
    (net (code "50") (name "TCK") (class "Default")
      (node (ref "IC4") (pin "49") (pinfunction "PA14_49") (pintype "bidirectional"))
      (node (ref "ST_LINK_CON1") (pin "2") (pinfunction "2_2") (pintype "bidirectional"))
    )
    (net (code "51") (name "TMS") (class "Default")
      (node (ref "IC4") (pin "46") (pinfunction "PA13_46") (pintype "bidirectional"))
      (node (ref "ST_LINK_CON1") (pin "5") (pinfunction "5_5") (pintype "bidirectional"))
    )
    (net (code "52") (name "USART_RX") (class "Default")
      (node (ref "IC4") (pin "17") (pinfunction "PA3_17") (pintype "bidirectional"))
      (node (ref "ST_LINK_CON1") (pin "8") (pinfunction "8_8") (pintype "bidirectional"))
    )
    (net (code "53") (name "USART_TX") (class "Default")
      (node (ref "IC4") (pin "16") (pinfunction "PA2_16") (pintype "bidirectional"))
      (node (ref "ST_LINK_CON1") (pin "7") (pinfunction "7_7") (pintype "bidirectional"))
    )
    (net (code "54") (name "VCC+") (class "Default")
      (node (ref "AD8426") (pin "16") (pinfunction "+VS_16") (pintype "passive"))
      (node (ref "AD8426") (pin "5") (pinfunction "+VS_2_5") (pintype "passive"))
      (node (ref "ADA4077_TRANSIMP") (pin "8") (pinfunction "V+_8") (pintype "power_in"))
      (node (ref "ADA4077_VEXT") (pin "8") (pinfunction "V+_8") (pintype "power_in"))
      (node (ref "ADG1419") (pin "4") (pinfunction "VDD_4") (pintype "power_in"))
      (node (ref "C_BP11") (pin "1") (pinfunction "1_1") (pintype "passive"))
      (node (ref "C_BP12") (pin "1") (pinfunction "1_1") (pintype "passive"))
      (node (ref "C_BP3") (pin "1") (pinfunction "1_1") (pintype "passive"))
      (node (ref "C_BP4") (pin "1") (pinfunction "1_1") (pintype "passive"))
      (node (ref "C_BP5") (pin "1") (pinfunction "1_1") (pintype "passive"))
      (node (ref "C_BP6") (pin "1") (pinfunction "1_1") (pintype "passive"))
      (node (ref "C_BP9") (pin "1") (pinfunction "1_1") (pintype "passive"))
      (node (ref "IC3") (pin "4") (pinfunction "R_4") (pintype "input"))
      (node (ref "IC3") (pin "8") (pinfunction "V+_8") (pintype "power_in"))
      (node (ref "POWER1") (pin "1") (pinfunction "S_1") (pintype "passive"))
      (node (ref "R15") (pin "1") (pinfunction "1_1") (pintype "passive"))
      (node (ref "RPI_CONN") (pin "16") (pinfunction "16_16") (pintype "bidirectional"))
      (node (ref "RPI_CONN") (pin "27") (pinfunction "27_27") (pintype "bidirectional"))
      (node (ref "SENOR_CON") (pin "12") (pinfunction "S_12") (pintype "passive"))
      (node (ref "VCC_IN_CONN") (pin "2") (pinfunction "2_2") (pintype "bidirectional"))
    )
    (net (code "55") (name "VCC-") (class "Default")
      (node (ref "AD8426") (pin "13") (pinfunction "-VS_2_13") (pintype "passive"))
      (node (ref "AD8426") (pin "8") (pinfunction "-VS_8") (pintype "passive"))
      (node (ref "ADA4077_TRANSIMP") (pin "4") (pinfunction "V-_4") (pintype "power_in"))
      (node (ref "ADA4077_VEXT") (pin "4") (pinfunction "V-_4") (pintype "power_in"))
      (node (ref "ADG1419") (pin "7") (pinfunction "VSS_7") (pintype "power_in"))
      (node (ref "C_BP1") (pin "2") (pinfunction "2_2") (pintype "passive"))
      (node (ref "C_BP10") (pin "2") (pinfunction "2_2") (pintype "passive"))
      (node (ref "C_BP2") (pin "1") (pinfunction "1_1") (pintype "passive"))
      (node (ref "C_BP7") (pin "1") (pinfunction "1_1") (pintype "passive"))
      (node (ref "C_BP8") (pin "1") (pinfunction "1_1") (pintype "passive"))
      (node (ref "C_CHARGE2") (pin "1") (pinfunction "1_1") (pintype "passive"))
      (node (ref "D5") (pin "A") (pinfunction "A_A") (pintype "passive"))
    )
    (net (code "56") (name "VDD") (class "Default")
      (node (ref "3V3_LS1") (pin "4") (pinfunction "VOUT_4") (pintype "output"))
      (node (ref "C3") (pin "1") (pinfunction "1_1") (pintype "bidirectional"))
      (node (ref "C6") (pin "1") (pinfunction "1_1") (pintype "bidirectional"))
      (node (ref "C7") (pin "1") (pinfunction "1_1") (pintype "bidirectional"))
      (node (ref "FB3") (pin "1") (pinfunction "1_1") (pintype "bidirectional"))
      (node (ref "IC4") (pin "1") (pinfunction "VBAT_1") (pintype "power_in"))
      (node (ref "IC4") (pin "19") (pinfunction "VDD_1_19") (pintype "power_in"))
      (node (ref "IC4") (pin "32") (pinfunction "VDD_2_32") (pintype "power_in"))
      (node (ref "IC4") (pin "48") (pinfunction "VDD_3_48") (pintype "power_in"))
      (node (ref "IC4") (pin "64") (pinfunction "VDD_4_64") (pintype "power_in"))
      (node (ref "MUC_CON") (pin "1") (pinfunction "1_1") (pintype "passive"))
      (node (ref "PRESSURE") (pin "2") (pinfunction "VDD_2") (pintype "bidirectional"))
      (node (ref "R1") (pin "2") (pinfunction "2_2") (pintype "passive"))
      (node (ref "R10") (pin "1") (pinfunction "1_1") (pintype "passive"))
      (node (ref "R21") (pin "2") (pinfunction "2_2") (pintype "passive"))
      (node (ref "R9") (pin "1") (pinfunction "1_1") (pintype "passive"))
      (node (ref "RPI_CONN") (pin "25") (pinfunction "25_25") (pintype "bidirectional"))
      (node (ref "SENOR_CON") (pin "1") (pinfunction "S_1") (pintype "passive"))
      (node (ref "ST_LINK_CON1") (pin "1") (pinfunction "1_1") (pintype "bidirectional"))
    )
    (net (code "57") (name "VEXT") (class "Default")
      (node (ref "C28") (pin "1") (pinfunction "1_1") (pintype "passive"))
      (node (ref "R14") (pin "1") (pinfunction "1_1") (pintype "passive"))
      (node (ref "R_CLIMIT") (pin "2") (pinfunction "2_2") (pintype "passive"))
      (node (ref "VEXT") (pin "1") (pinfunction "P_1") (pintype "passive"))
    )
    (net (code "58") (name "VEXT+") (class "Default")
      (node (ref "ADA4077_VEXT") (pin "1") (pinfunction "OUTA_1") (pintype "output"))
      (node (ref "ADA4077_VEXT") (pin "2") (pinfunction "-INA_2") (pintype "input"))
      (node (ref "ADG1419") (pin "8") (pinfunction "SB_8") (pintype "bidirectional"))
      (node (ref "R3") (pin "2") (pinfunction "2_2") (pintype "passive"))
    )
    (net (code "59") (name "VEXT-") (class "Default")
      (node (ref "ADA4077_VEXT") (pin "7") (pinfunction "OUTB_7") (pintype "output"))
      (node (ref "ADG1419") (pin "2") (pinfunction "SA_2") (pintype "bidirectional"))
      (node (ref "C2") (pin "1") (pinfunction "1_1") (pintype "passive"))
      (node (ref "R4") (pin "1") (pinfunction "1_1") (pintype "passive"))
    )
    (net (code "60") (name "VOLTAGE_ADC") (class "Default")
      (node (ref "AD8426") (pin "15") (pinfunction "OUT1_15") (pintype "passive"))
      (node (ref "SENOR_CON") (pin "10") (pinfunction "S_10") (pintype "passive"))
    )
    (net (code "61") (name "VOLTAGE_ADC_M") (class "Default")
      (node (ref "IC4") (pin "10") (pinfunction "PC2_10") (pintype "bidirectional"))
      (node (ref "MUC_CON") (pin "10") (pinfunction "10_10") (pintype "passive"))
      (node (ref "RPI_CONN") (pin "18") (pinfunction "18_18") (pintype "bidirectional"))
    )
    (net (code "62") (name "VREF") (class "Default")
      (node (ref "AD8426") (pin "6") (pinfunction "REF1_6") (pintype "passive"))
      (node (ref "AD8426") (pin "7") (pinfunction "REF2_7") (pintype "passive"))
      (node (ref "ADA4077_TRANSIMP") (pin "6") (pinfunction "-INB_6") (pintype "input"))
      (node (ref "ADA4077_TRANSIMP") (pin "7") (pinfunction "OUTB_7") (pintype "output"))
    )
    (net (code "63") (name "V_CURRENT") (class "Default")
      (node (ref "AD8426") (pin "9") (pinfunction "+IN2_9") (pintype "passive"))
      (node (ref "ADA4077_TRANSIMP") (pin "1") (pinfunction "OUTA_1") (pintype "output"))
      (node (ref "C1") (pin "2") (pinfunction "2_2") (pintype "passive"))
      (node (ref "R_CURRENT") (pin "1") (pinfunction "1_1") (pintype "passive"))
    )
    (net (code "64") (name "V_VOLTAGE+") (class "Default")
      (node (ref "AD8426") (pin "4") (pinfunction "+IN1_4") (pintype "passive"))
      (node (ref "V-") (pin "1") (pinfunction "P_1") (pintype "passive"))
    )
    (net (code "65") (name "V_VOLTAGE-") (class "Default")
      (node (ref "AD8426") (pin "1") (pinfunction "-IN1_1") (pintype "passive"))
      (node (ref "V+") (pin "1") (pinfunction "P_1") (pintype "passive"))
    )
    (net (code "66") (name "ZAC_WIRE") (class "Default")
      (node (ref "SENOR_CON") (pin "5") (pinfunction "S_5") (pintype "passive"))
      (node (ref "TEMPERATURE") (pin "2") (pinfunction "S_2") (pintype "passive"))
    )
    (net (code "67") (name "ZAC_WIRE_M") (class "Default")
      (node (ref "IC4") (pin "37") (pinfunction "PC6_37") (pintype "bidirectional"))
      (node (ref "MUC_CON") (pin "5") (pinfunction "5_5") (pintype "passive"))
      (node (ref "RPI_CONN") (pin "17") (pinfunction "17_17") (pintype "bidirectional"))
    )
    (net (code "68") (name "unconnected-(3V3_LS1-NC-Pad5)") (class "Default")
      (node (ref "3V3_LS1") (pin "5") (pinfunction "NC_5") (pintype "no_connect"))
    )
    (net (code "69") (name "unconnected-(3V3_LS1-PG-Pad3)") (class "Default")
      (node (ref "3V3_LS1") (pin "3") (pinfunction "PG_3") (pintype "output"))
    )
    (net (code "70") (name "unconnected-(ADG1419-NC-Pad5)") (class "Default")
      (node (ref "ADG1419") (pin "5") (pinfunction "NC_5") (pintype "no_connect"))
    )
    (net (code "71") (name "unconnected-(IC4-PA0-Pad14)") (class "Default")
      (node (ref "IC4") (pin "14") (pinfunction "PA0_14") (pintype "bidirectional"))
    )
    (net (code "72") (name "unconnected-(IC4-PA1-Pad15)") (class "Default")
      (node (ref "IC4") (pin "15") (pinfunction "PA1_15") (pintype "bidirectional"))
    )
    (net (code "73") (name "unconnected-(IC4-PA5-Pad21)") (class "Default")
      (node (ref "IC4") (pin "21") (pinfunction "PA5_21") (pintype "bidirectional"))
    )
    (net (code "74") (name "unconnected-(IC4-PA6-Pad22)") (class "Default")
      (node (ref "IC4") (pin "22") (pinfunction "PA6_22") (pintype "bidirectional"))
    )
    (net (code "75") (name "unconnected-(IC4-PA7-Pad23)") (class "Default")
      (node (ref "IC4") (pin "23") (pinfunction "PA7_23") (pintype "bidirectional"))
    )
    (net (code "76") (name "unconnected-(IC4-PA8-Pad41)") (class "Default")
      (node (ref "IC4") (pin "41") (pinfunction "PA8_41") (pintype "bidirectional"))
    )
    (net (code "77") (name "unconnected-(IC4-PA11-Pad44)") (class "Default")
      (node (ref "IC4") (pin "44") (pinfunction "PA11_44") (pintype "bidirectional"))
    )
    (net (code "78") (name "unconnected-(IC4-PA15-Pad50)") (class "Default")
      (node (ref "IC4") (pin "50") (pinfunction "PA15_50") (pintype "bidirectional"))
    )
    (net (code "79") (name "unconnected-(IC4-PB0-Pad26)") (class "Default")
      (node (ref "IC4") (pin "26") (pinfunction "PB0_26") (pintype "bidirectional"))
    )
    (net (code "80") (name "unconnected-(IC4-PB1-Pad27)") (class "Default")
      (node (ref "IC4") (pin "27") (pinfunction "PB1_27") (pintype "bidirectional"))
    )
    (net (code "81") (name "unconnected-(IC4-PB2-Pad28)") (class "Default")
      (node (ref "IC4") (pin "28") (pinfunction "PB2_28") (pintype "bidirectional"))
    )
    (net (code "82") (name "unconnected-(IC4-PB9-Pad62)") (class "Default")
      (node (ref "IC4") (pin "62") (pinfunction "PB9_62") (pintype "bidirectional"))
    )
    (net (code "83") (name "unconnected-(IC4-PB10-Pad29)") (class "Default")
      (node (ref "IC4") (pin "29") (pinfunction "PB10_29") (pintype "bidirectional"))
    )
    (net (code "84") (name "unconnected-(IC4-PB11-Pad30)") (class "Default")
      (node (ref "IC4") (pin "30") (pinfunction "PB11_30") (pintype "bidirectional"))
    )
    (net (code "85") (name "unconnected-(IC4-PB12-Pad33)") (class "Default")
      (node (ref "IC4") (pin "33") (pinfunction "PB12_33") (pintype "bidirectional"))
    )
    (net (code "86") (name "unconnected-(IC4-PB13-Pad34)") (class "Default")
      (node (ref "IC4") (pin "34") (pinfunction "PB13_34") (pintype "bidirectional"))
    )
    (net (code "87") (name "unconnected-(IC4-PB14-Pad35)") (class "Default")
      (node (ref "IC4") (pin "35") (pinfunction "PB14_35") (pintype "bidirectional"))
    )
    (net (code "88") (name "unconnected-(IC4-PB15-Pad36)") (class "Default")
      (node (ref "IC4") (pin "36") (pinfunction "PB15_36") (pintype "bidirectional"))
    )
    (net (code "89") (name "unconnected-(IC4-PC0-Pad8)") (class "Default")
      (node (ref "IC4") (pin "8") (pinfunction "PC0_8") (pintype "bidirectional"))
    )
    (net (code "90") (name "unconnected-(IC4-PC3-Pad11)") (class "Default")
      (node (ref "IC4") (pin "11") (pinfunction "PC3_11") (pintype "bidirectional"))
    )
    (net (code "91") (name "unconnected-(IC4-PC4-Pad24)") (class "Default")
      (node (ref "IC4") (pin "24") (pinfunction "PC4_24") (pintype "bidirectional"))
    )
    (net (code "92") (name "unconnected-(IC4-PC5-Pad25)") (class "Default")
      (node (ref "IC4") (pin "25") (pinfunction "PC5_25") (pintype "bidirectional"))
    )
    (net (code "93") (name "unconnected-(IC4-PC7-Pad38)") (class "Default")
      (node (ref "IC4") (pin "38") (pinfunction "PC7_38") (pintype "bidirectional"))
    )
    (net (code "94") (name "unconnected-(IC4-PC8-Pad39)") (class "Default")
      (node (ref "IC4") (pin "39") (pinfunction "PC8_39") (pintype "bidirectional"))
    )
    (net (code "95") (name "unconnected-(IC4-PC9-Pad40)") (class "Default")
      (node (ref "IC4") (pin "40") (pinfunction "PC9_40") (pintype "bidirectional"))
    )
    (net (code "96") (name "unconnected-(IC4-PC10-Pad51)") (class "Default")
      (node (ref "IC4") (pin "51") (pinfunction "PC10_51") (pintype "bidirectional"))
    )
    (net (code "97") (name "unconnected-(IC4-PC11-Pad52)") (class "Default")
      (node (ref "IC4") (pin "52") (pinfunction "PC11_52") (pintype "bidirectional"))
    )
    (net (code "98") (name "unconnected-(IC4-PC12-Pad53)") (class "Default")
      (node (ref "IC4") (pin "53") (pinfunction "PC12_53") (pintype "bidirectional"))
    )
    (net (code "99") (name "unconnected-(IC4-PC13-Pad2)") (class "Default")
      (node (ref "IC4") (pin "2") (pinfunction "PC13_2") (pintype "bidirectional"))
    )
    (net (code "100") (name "unconnected-(IC4-PC14-OSC32_IN-Pad3)") (class "Default")
      (node (ref "IC4") (pin "3") (pinfunction "PC14-OSC32_IN_3") (pintype "bidirectional"))
    )
    (net (code "101") (name "unconnected-(IC4-PC15-OSC32_OUT-Pad4)") (class "Default")
      (node (ref "IC4") (pin "4") (pinfunction "PC15-OSC32_OUT_4") (pintype "bidirectional"))
    )
    (net (code "102") (name "unconnected-(IC4-PD2-Pad54)") (class "Default")
      (node (ref "IC4") (pin "54") (pinfunction "PD2_54") (pintype "bidirectional"))
    )
    (net (code "103") (name "unconnected-(IC4-PF0-OSC_IN-Pad5)") (class "Default")
      (node (ref "IC4") (pin "5") (pinfunction "PF0-OSC_IN_5") (pintype "bidirectional"))
    )
    (net (code "104") (name "unconnected-(IC4-PF1-OSC_OUT-Pad6)") (class "Default")
      (node (ref "IC4") (pin "6") (pinfunction "PF1-OSC_OUT_6") (pintype "bidirectional"))
    )
    (net (code "105") (name "unconnected-(MUC_CON-Pad13)") (class "Default")
      (node (ref "MUC_CON") (pin "13") (pinfunction "13_13") (pintype "passive"))
    )
    (net (code "106") (name "unconnected-(MUC_CON-Pad14)") (class "Default")
      (node (ref "MUC_CON") (pin "14") (pinfunction "14_14") (pintype "passive"))
    )
    (net (code "107") (name "unconnected-(RPI_CONN-Pad1)") (class "Default")
      (node (ref "RPI_CONN") (pin "1") (pinfunction "1_1") (pintype "bidirectional"))
    )
    (net (code "108") (name "unconnected-(RPI_CONN-Pad4)") (class "Default")
      (node (ref "RPI_CONN") (pin "4") (pinfunction "4_4") (pintype "bidirectional"))
    )
    (net (code "109") (name "unconnected-(RPI_CONN-Pad8)") (class "Default")
      (node (ref "RPI_CONN") (pin "8") (pinfunction "8_8") (pintype "bidirectional"))
    )
    (net (code "110") (name "unconnected-(RPI_CONN-Pad9)") (class "Default")
      (node (ref "RPI_CONN") (pin "9") (pinfunction "9_9") (pintype "bidirectional"))
    )
    (net (code "111") (name "unconnected-(RPI_CONN-Pad10)") (class "Default")
      (node (ref "RPI_CONN") (pin "10") (pinfunction "10_10") (pintype "bidirectional"))
    )
    (net (code "112") (name "unconnected-(RPI_CONN-Pad12)") (class "Default")
      (node (ref "RPI_CONN") (pin "12") (pinfunction "12_12") (pintype "bidirectional"))
    )
    (net (code "113") (name "unconnected-(RPI_CONN-Pad13)") (class "Default")
      (node (ref "RPI_CONN") (pin "13") (pinfunction "13_13") (pintype "bidirectional"))
    )
    (net (code "114") (name "unconnected-(RPI_CONN-Pad14)") (class "Default")
      (node (ref "RPI_CONN") (pin "14") (pinfunction "14_14") (pintype "bidirectional"))
    )
    (net (code "115") (name "unconnected-(RPI_CONN-Pad29)") (class "Default")
      (node (ref "RPI_CONN") (pin "29") (pinfunction "29_29") (pintype "bidirectional"))
    )
    (net (code "116") (name "unconnected-(RPI_CONN-Pad30)") (class "Default")
      (node (ref "RPI_CONN") (pin "30") (pinfunction "30_30") (pintype "bidirectional"))
    )
    (net (code "117") (name "unconnected-(RPI_CONN-Pad31)") (class "Default")
      (node (ref "RPI_CONN") (pin "31") (pinfunction "31_31") (pintype "bidirectional"))
    )
    (net (code "118") (name "unconnected-(RPI_CONN-Pad32)") (class "Default")
      (node (ref "RPI_CONN") (pin "32") (pinfunction "32_32") (pintype "bidirectional"))
    )
    (net (code "119") (name "unconnected-(RPI_CONN-Pad33)") (class "Default")
      (node (ref "RPI_CONN") (pin "33") (pinfunction "33_33") (pintype "bidirectional"))
    )
    (net (code "120") (name "unconnected-(RPI_CONN-Pad34)") (class "Default")
      (node (ref "RPI_CONN") (pin "34") (pinfunction "34_34") (pintype "bidirectional"))
    )
    (net (code "121") (name "unconnected-(RPI_CONN-Pad35)") (class "Default")
      (node (ref "RPI_CONN") (pin "35") (pinfunction "35_35") (pintype "bidirectional"))
    )
    (net (code "122") (name "unconnected-(RPI_CONN-Pad36)") (class "Default")
      (node (ref "RPI_CONN") (pin "36") (pinfunction "36_36") (pintype "bidirectional"))
    )
    (net (code "123") (name "unconnected-(RPI_CONN-Pad37)") (class "Default")
      (node (ref "RPI_CONN") (pin "37") (pinfunction "37_37") (pintype "bidirectional"))
    )
    (net (code "124") (name "unconnected-(RPI_CONN-Pad38)") (class "Default")
      (node (ref "RPI_CONN") (pin "38") (pinfunction "38_38") (pintype "bidirectional"))
    )
    (net (code "125") (name "unconnected-(RPI_CONN-Pad39)") (class "Default")
      (node (ref "RPI_CONN") (pin "39") (pinfunction "39_39") (pintype "bidirectional"))
    )
    (net (code "126") (name "unconnected-(RPI_CONN-Pad40)") (class "Default")
      (node (ref "RPI_CONN") (pin "40") (pinfunction "40_40") (pintype "bidirectional"))
    )
  )
)
